# analogClock.net
KiCad netlist of a schematic drawn in EAGLE
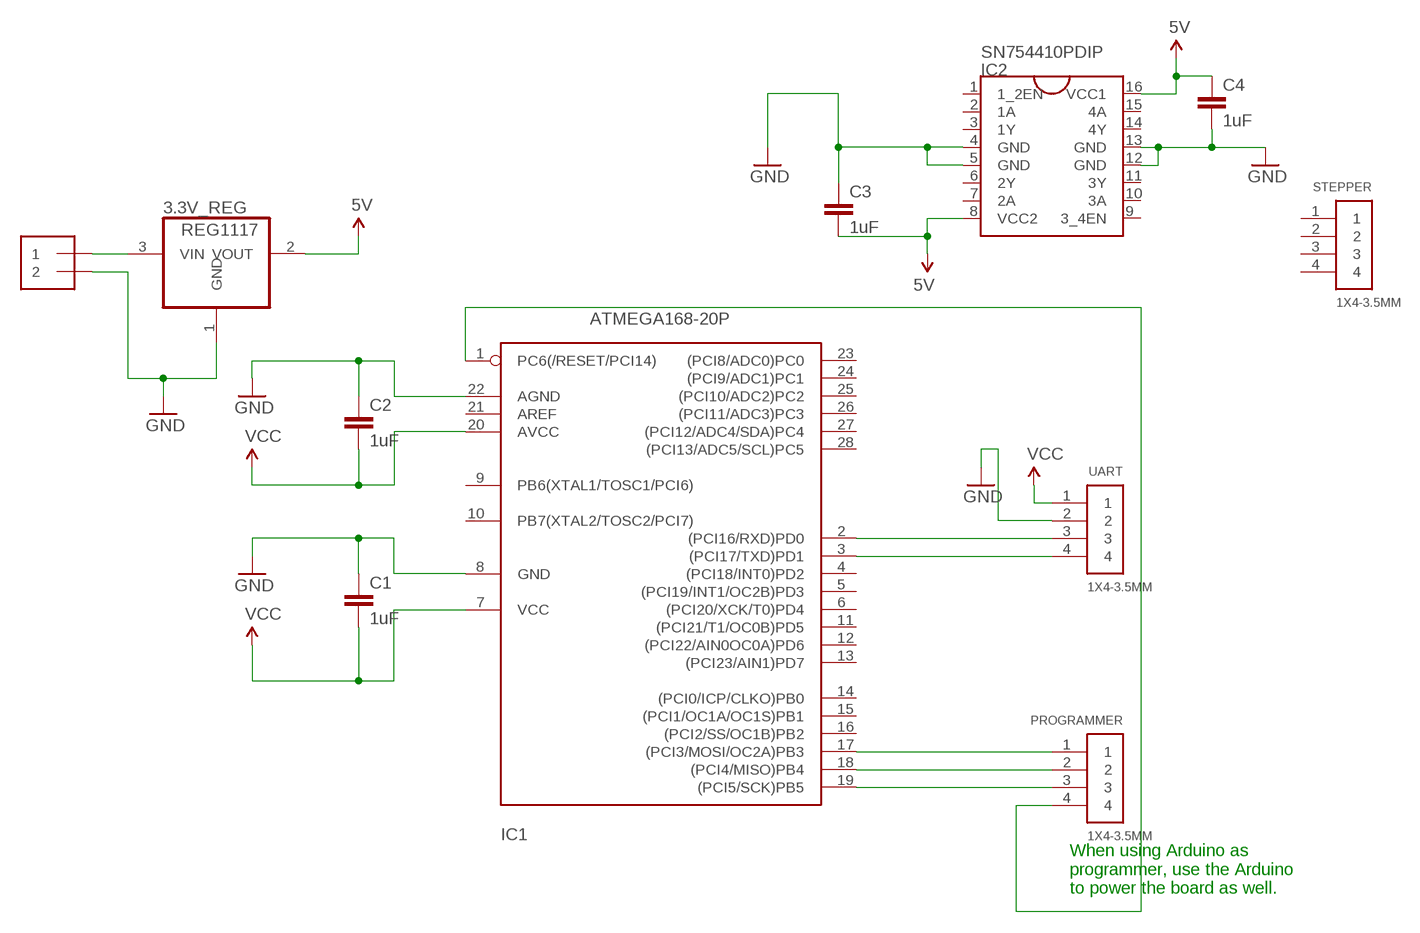
[diagram p0: schematic, sheet 1]

(export (version "E")
  (design (tool "Eeschema 10.0.6"))
  (components
    (comp (ref "3.3V_REG")
      (value "REG1117")
      (footprint "eagle-import:SOT223")
      (libsource (lib "eagle-import") (part "REG1117"))
    )
    (comp (ref "C1")
      (value "1uF")
      (footprint "eagle-import:CAP-PTH-SMALL")
      (libsource (lib "eagle-import") (part "CAPPTH"))
    )
    (comp (ref "C2")
      (value "1uF")
      (footprint "eagle-import:CAP-PTH-SMALL")
      (libsource (lib "eagle-import") (part "CAPPTH"))
    )
    (comp (ref "C3")
      (value "1uF")
      (footprint "eagle-import:CAP-PTH-SMALL")
      (libsource (lib "eagle-import") (part "CAPPTH"))
    )
    (comp (ref "C4")
      (value "1uF")
      (footprint "eagle-import:CAP-PTH-SMALL")
      (libsource (lib "eagle-import") (part "CAPPTH"))
    )
    (comp (ref "IC1")
      (value "ATMEGA168-20P")
      (footprint "eagle-import:DIL28-3")
      (libsource (lib "eagle-import") (part "ATMEGA168P-20"))
    )
    (comp (ref "IC2")
      (value "SN754410PDIP")
      (footprint "eagle-import:DIL16")
      (libsource (lib "eagle-import") (part "SN754410PDIP"))
    )
    (comp (ref "POWER_IN")
      (value "1X2-3.5MM")
      (footprint "eagle-import:1X2-3.5MM")
      (libsource (lib "eagle-import") (part "1X2-3.5MM"))
    )
    (comp (ref "PROGRAMMER")
      (value "1X4-3.5MM")
      (footprint "eagle-import:1X04-3.5MM")
      (libsource (lib "eagle-import") (part "1X4-3.5MM"))
    )
    (comp (ref "STEPPER")
      (value "1X4-3.5MM")
      (footprint "eagle-import:1X04-3.5MM")
      (libsource (lib "eagle-import") (part "1X4-3.5MM"))
    )
    (comp (ref "UART")
      (value "1X4-3.5MM")
      (footprint "eagle-import:1X04-3.5MM")
      (libsource (lib "eagle-import") (part "1X4-3.5MM"))
    )
  )
  (nets
    (net (code "1") (name "5V") (class "Default")
      (node (ref "3.3V_REG") (pin "2") (pinfunction "VOUT_2") (pintype "output"))
      (node (ref "C3") (pin "2") (pinfunction "2_2") (pintype "passive"))
      (node (ref "C4") (pin "1") (pinfunction "1_1") (pintype "passive"))
      (node (ref "IC2") (pin "16") (pinfunction "VCC1_16") (pintype "bidirectional"))
      (node (ref "IC2") (pin "8") (pinfunction "VCC2_8") (pintype "bidirectional"))
    )
    (net (code "2") (name "GND") (class "Default")
      (node (ref "3.3V_REG") (pin "1") (pinfunction "GND_1") (pintype "power_in"))
      (node (ref "C1") (pin "1") (pinfunction "1_1") (pintype "passive"))
      (node (ref "C2") (pin "1") (pinfunction "1_1") (pintype "passive"))
      (node (ref "C3") (pin "1") (pinfunction "1_1") (pintype "passive"))
      (node (ref "C4") (pin "2") (pinfunction "2_2") (pintype "passive"))
      (node (ref "IC1") (pin "22") (pinfunction "AGND_22") (pintype "bidirectional"))
      (node (ref "IC1") (pin "8") (pinfunction "GND_8") (pintype "bidirectional"))
      (node (ref "IC2") (pin "12") (pinfunction "GND_12") (pintype "bidirectional"))
      (node (ref "IC2") (pin "13") (pinfunction "GND_13") (pintype "bidirectional"))
      (node (ref "IC2") (pin "4") (pinfunction "GND_4") (pintype "bidirectional"))
      (node (ref "IC2") (pin "5") (pinfunction "GND_5") (pintype "bidirectional"))
      (node (ref "POWER_IN") (pin "2") (pinfunction "2_2") (pintype "passive"))
      (node (ref "UART") (pin "2") (pinfunction "2_2") (pintype "bidirectional"))
    )
    (net (code "3") (name "Net-(3.3V_REG-VIN)") (class "Default")
      (node (ref "3.3V_REG") (pin "3") (pinfunction "VIN_3") (pintype "input"))
      (node (ref "POWER_IN") (pin "1") (pinfunction "1_1") (pintype "passive"))
    )
    (net (code "4") (name "Net-(IC1-(PCI3{slash}MOSI{slash}OC2A)PB3)") (class "Default")
      (node (ref "IC1") (pin "17") (pinfunction "(PCI3/MOSI/OC2A)PB3_17") (pintype "bidirectional"))
      (node (ref "PROGRAMMER") (pin "1") (pinfunction "1_1") (pintype "bidirectional"))
    )
    (net (code "5") (name "Net-(IC1-(PCI4{slash}MISO)PB4)") (class "Default")
      (node (ref "IC1") (pin "18") (pinfunction "(PCI4/MISO)PB4_18") (pintype "bidirectional"))
      (node (ref "PROGRAMMER") (pin "2") (pinfunction "2_2") (pintype "bidirectional"))
    )
    (net (code "6") (name "Net-(IC1-(PCI5{slash}SCK)PB5)") (class "Default")
      (node (ref "IC1") (pin "19") (pinfunction "(PCI5/SCK)PB5_19") (pintype "bidirectional"))
      (node (ref "PROGRAMMER") (pin "3") (pinfunction "3_3") (pintype "bidirectional"))
    )
    (net (code "7") (name "Net-(IC1-(PCI16{slash}RXD)PD0)") (class "Default")
      (node (ref "IC1") (pin "2") (pinfunction "(PCI16/RXD)PD0_2") (pintype "bidirectional"))
      (node (ref "UART") (pin "3") (pinfunction "3_3") (pintype "bidirectional"))
    )
    (net (code "8") (name "Net-(IC1-(PCI17{slash}TXD)PD1)") (class "Default")
      (node (ref "IC1") (pin "3") (pinfunction "(PCI17/TXD)PD1_3") (pintype "bidirectional"))
      (node (ref "UART") (pin "4") (pinfunction "4_4") (pintype "bidirectional"))
    )
    (net (code "9") (name "Net-(IC1-PC6({slash}RESET{slash}PCI14))") (class "Default")
      (node (ref "IC1") (pin "1") (pinfunction "PC6(/RESET/PCI14)_1") (pintype "bidirectional"))
      (node (ref "PROGRAMMER") (pin "4") (pinfunction "4_4") (pintype "bidirectional"))
    )
    (net (code "10") (name "VCC") (class "Default")
      (node (ref "C1") (pin "2") (pinfunction "2_2") (pintype "passive"))
      (node (ref "C2") (pin "2") (pinfunction "2_2") (pintype "passive"))
      (node (ref "IC1") (pin "20") (pinfunction "AVCC_20") (pintype "bidirectional"))
      (node (ref "IC1") (pin "7") (pinfunction "VCC_7") (pintype "bidirectional"))
      (node (ref "UART") (pin "1") (pinfunction "1_1") (pintype "bidirectional"))
    )
    (net (code "11") (name "unconnected-(IC1-(PCI0{slash}ICP{slash}CLKO)PB0-Pad14)") (class "Default")
      (node (ref "IC1") (pin "14") (pinfunction "(PCI0/ICP/CLKO)PB0_14") (pintype "bidirectional"))
    )
    (net (code "12") (name "unconnected-(IC1-(PCI1{slash}OC1A{slash}OC1S)PB1-Pad15)") (class "Default")
      (node (ref "IC1") (pin "15") (pinfunction "(PCI1/OC1A/OC1S)PB1_15") (pintype "bidirectional"))
    )
    (net (code "13") (name "unconnected-(IC1-(PCI2{slash}SS{slash}OC1B)PB2-Pad16)") (class "Default")
      (node (ref "IC1") (pin "16") (pinfunction "(PCI2/SS/OC1B)PB2_16") (pintype "bidirectional"))
    )
    (net (code "14") (name "unconnected-(IC1-(PCI8{slash}ADC0)PC0-Pad23)") (class "Default")
      (node (ref "IC1") (pin "23") (pinfunction "(PCI8/ADC0)PC0_23") (pintype "bidirectional"))
    )
    (net (code "15") (name "unconnected-(IC1-(PCI9{slash}ADC1)PC1-Pad24)") (class "Default")
      (node (ref "IC1") (pin "24") (pinfunction "(PCI9/ADC1)PC1_24") (pintype "bidirectional"))
    )
    (net (code "16") (name "unconnected-(IC1-(PCI10{slash}ADC2)PC2-Pad25)") (class "Default")
      (node (ref "IC1") (pin "25") (pinfunction "(PCI10/ADC2)PC2_25") (pintype "bidirectional"))
    )
    (net (code "17") (name "unconnected-(IC1-(PCI11{slash}ADC3)PC3-Pad26)") (class "Default")
      (node (ref "IC1") (pin "26") (pinfunction "(PCI11/ADC3)PC3_26") (pintype "bidirectional"))
    )
    (net (code "18") (name "unconnected-(IC1-(PCI12{slash}ADC4{slash}SDA)PC4-Pad27)") (class "Default")
      (node (ref "IC1") (pin "27") (pinfunction "(PCI12/ADC4/SDA)PC4_27") (pintype "bidirectional"))
    )
    (net (code "19") (name "unconnected-(IC1-(PCI13{slash}ADC5{slash}SCL)PC5-Pad28)") (class "Default")
      (node (ref "IC1") (pin "28") (pinfunction "(PCI13/ADC5/SCL)PC5_28") (pintype "bidirectional"))
    )
    (net (code "20") (name "unconnected-(IC1-(PCI18{slash}INT0)PD2-Pad4)") (class "Default")
      (node (ref "IC1") (pin "4") (pinfunction "(PCI18/INT0)PD2_4") (pintype "bidirectional"))
    )
    (net (code "21") (name "unconnected-(IC1-(PCI19{slash}INT1{slash}OC2B)PD3-Pad5)") (class "Default")
      (node (ref "IC1") (pin "5") (pinfunction "(PCI19/INT1/OC2B)PD3_5") (pintype "bidirectional"))
    )
    (net (code "22") (name "unconnected-(IC1-(PCI20{slash}XCK{slash}T0)PD4-Pad6)") (class "Default")
      (node (ref "IC1") (pin "6") (pinfunction "(PCI20/XCK/T0)PD4_6") (pintype "bidirectional"))
    )
    (net (code "23") (name "unconnected-(IC1-(PCI21{slash}T1{slash}OC0B)PD5-Pad11)") (class "Default")
      (node (ref "IC1") (pin "11") (pinfunction "(PCI21/T1/OC0B)PD5_11") (pintype "bidirectional"))
    )
    (net (code "24") (name "unconnected-(IC1-(PCI22{slash}AIN0OC0A)PD6-Pad12)") (class "Default")
      (node (ref "IC1") (pin "12") (pinfunction "(PCI22/AIN0OC0A)PD6_12") (pintype "bidirectional"))
    )
    (net (code "25") (name "unconnected-(IC1-(PCI23{slash}AIN1)PD7-Pad13)") (class "Default")
      (node (ref "IC1") (pin "13") (pinfunction "(PCI23/AIN1)PD7_13") (pintype "bidirectional"))
    )
    (net (code "26") (name "unconnected-(IC1-AREF-Pad21)") (class "Default")
      (node (ref "IC1") (pin "21") (pinfunction "AREF_21") (pintype "bidirectional"))
    )
    (net (code "27") (name "unconnected-(IC1-PB6(XTAL1{slash}TOSC1{slash}PCI6)-Pad9)") (class "Default")
      (node (ref "IC1") (pin "9") (pinfunction "PB6(XTAL1/TOSC1/PCI6)_9") (pintype "bidirectional"))
    )
    (net (code "28") (name "unconnected-(IC1-PB7(XTAL2{slash}TOSC2{slash}PCI7)-Pad10)") (class "Default")
      (node (ref "IC1") (pin "10") (pinfunction "PB7(XTAL2/TOSC2/PCI7)_10") (pintype "bidirectional"))
    )
    (net (code "29") (name "unconnected-(IC2-1A-Pad2)") (class "Default")
      (node (ref "IC2") (pin "2") (pinfunction "1A_2") (pintype "bidirectional"))
    )
    (net (code "30") (name "unconnected-(IC2-1Y-Pad3)") (class "Default")
      (node (ref "IC2") (pin "3") (pinfunction "1Y_3") (pintype "bidirectional"))
    )
    (net (code "31") (name "unconnected-(IC2-1_2EN-Pad1)") (class "Default")
      (node (ref "IC2") (pin "1") (pinfunction "1_2EN_1") (pintype "bidirectional"))
    )
    (net (code "32") (name "unconnected-(IC2-2A-Pad7)") (class "Default")
      (node (ref "IC2") (pin "7") (pinfunction "2A_7") (pintype "bidirectional"))
    )
    (net (code "33") (name "unconnected-(IC2-2Y-Pad6)") (class "Default")
      (node (ref "IC2") (pin "6") (pinfunction "2Y_6") (pintype "bidirectional"))
    )
    (net (code "34") (name "unconnected-(IC2-3A-Pad10)") (class "Default")
      (node (ref "IC2") (pin "10") (pinfunction "3A_10") (pintype "bidirectional"))
    )
    (net (code "35") (name "unconnected-(IC2-3Y-Pad11)") (class "Default")
      (node (ref "IC2") (pin "11") (pinfunction "3Y_11") (pintype "bidirectional"))
    )
    (net (code "36") (name "unconnected-(IC2-3_4EN-Pad9)") (class "Default")
      (node (ref "IC2") (pin "9") (pinfunction "3_4EN_9") (pintype "bidirectional"))
    )
    (net (code "37") (name "unconnected-(IC2-4A-Pad15)") (class "Default")
      (node (ref "IC2") (pin "15") (pinfunction "4A_15") (pintype "bidirectional"))
    )
    (net (code "38") (name "unconnected-(IC2-4Y-Pad14)") (class "Default")
      (node (ref "IC2") (pin "14") (pinfunction "4Y_14") (pintype "bidirectional"))
    )
    (net (code "39") (name "unconnected-(STEPPER-Pad1)") (class "Default")
      (node (ref "STEPPER") (pin "1") (pinfunction "1_1") (pintype "bidirectional"))
    )
    (net (code "40") (name "unconnected-(STEPPER-Pad2)") (class "Default")
      (node (ref "STEPPER") (pin "2") (pinfunction "2_2") (pintype "bidirectional"))
    )
    (net (code "41") (name "unconnected-(STEPPER-Pad3)") (class "Default")
      (node (ref "STEPPER") (pin "3") (pinfunction "3_3") (pintype "bidirectional"))
    )
    (net (code "42") (name "unconnected-(STEPPER-Pad4)") (class "Default")
      (node (ref "STEPPER") (pin "4") (pinfunction "4_4") (pintype "bidirectional"))
    )
  )
)
